# WIBL.net
KiCad netlist of a schematic drawn in EAGLE
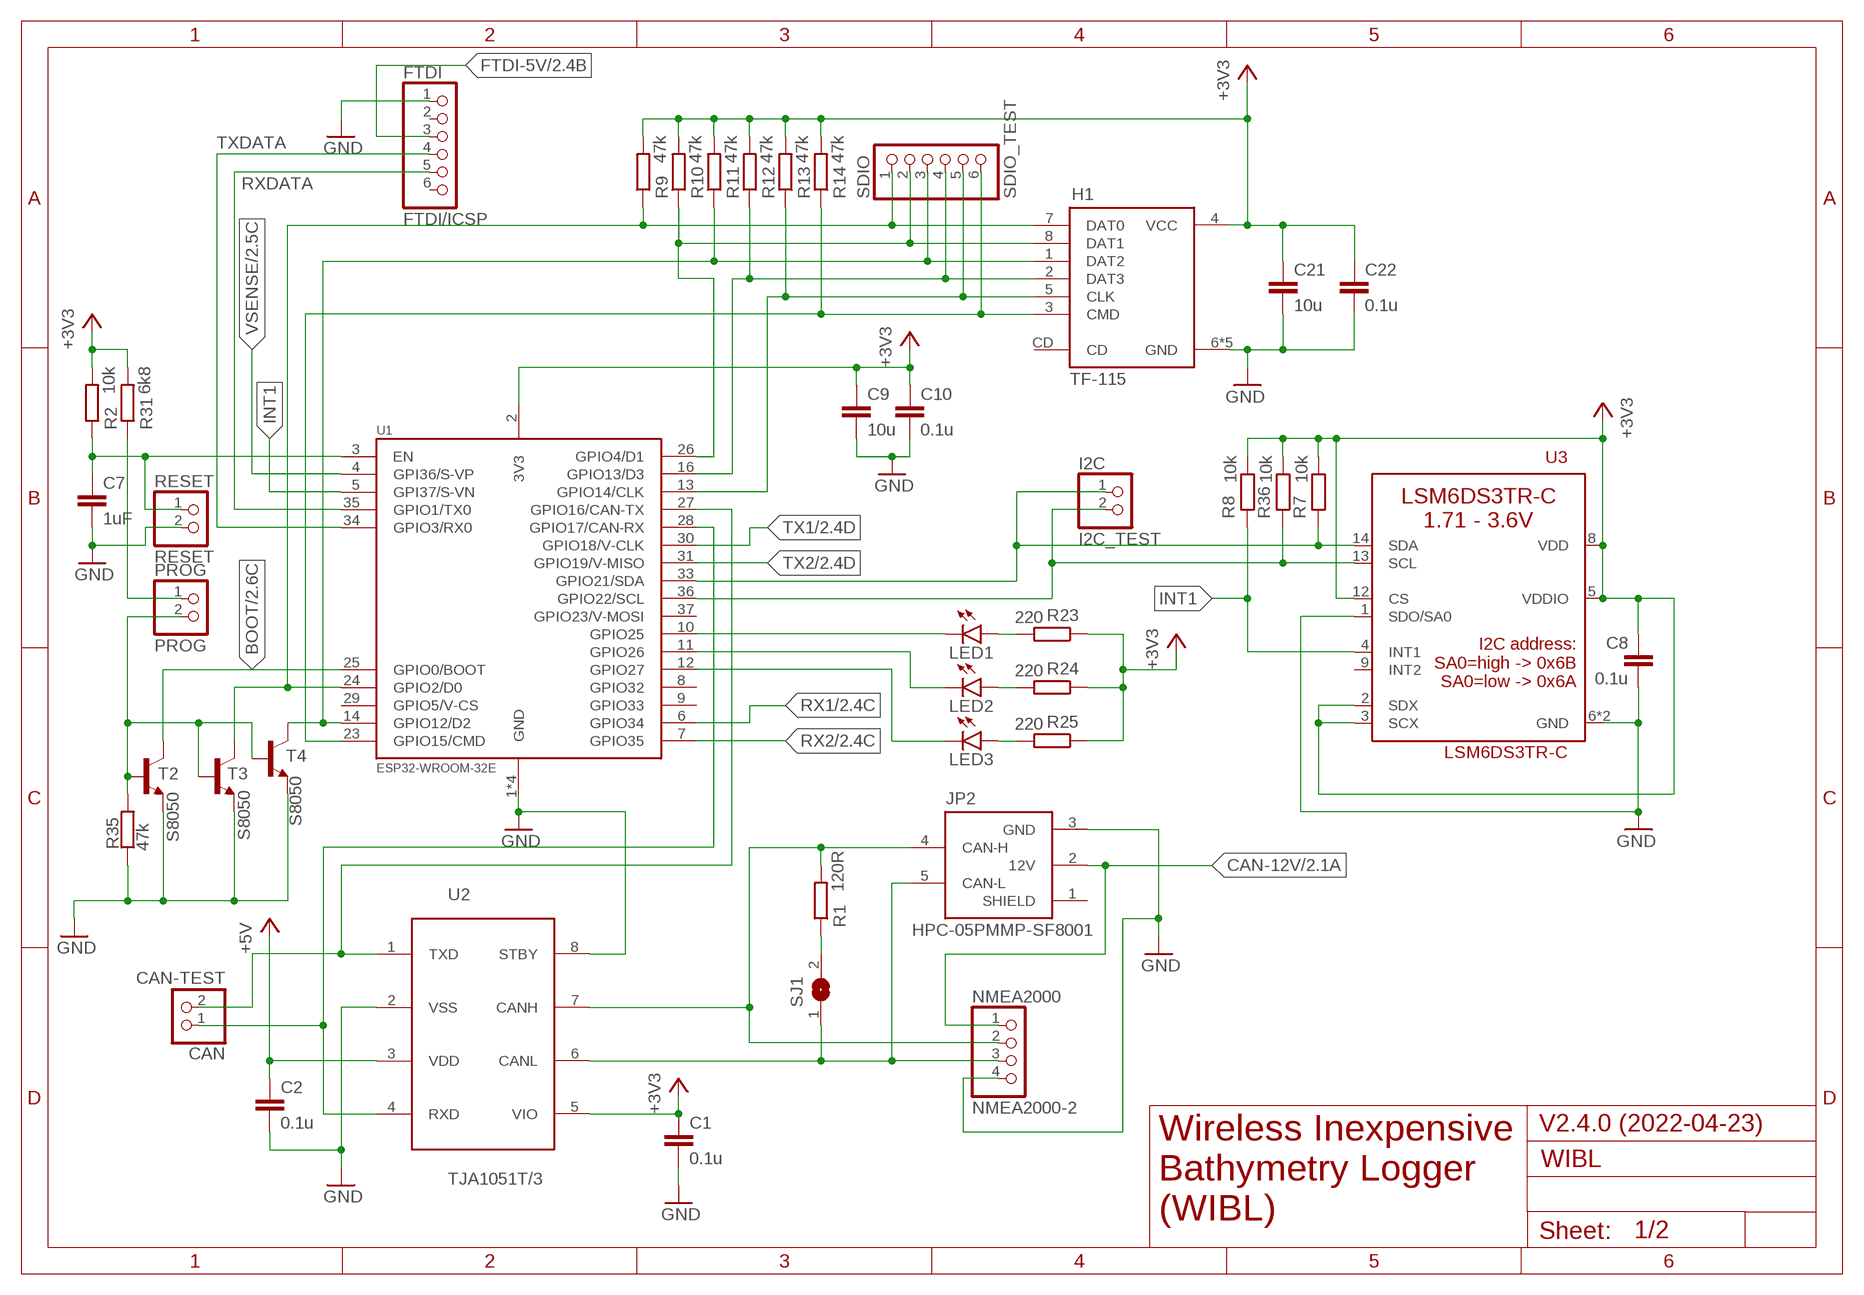
[diagram p0: schematic, sheet 1]
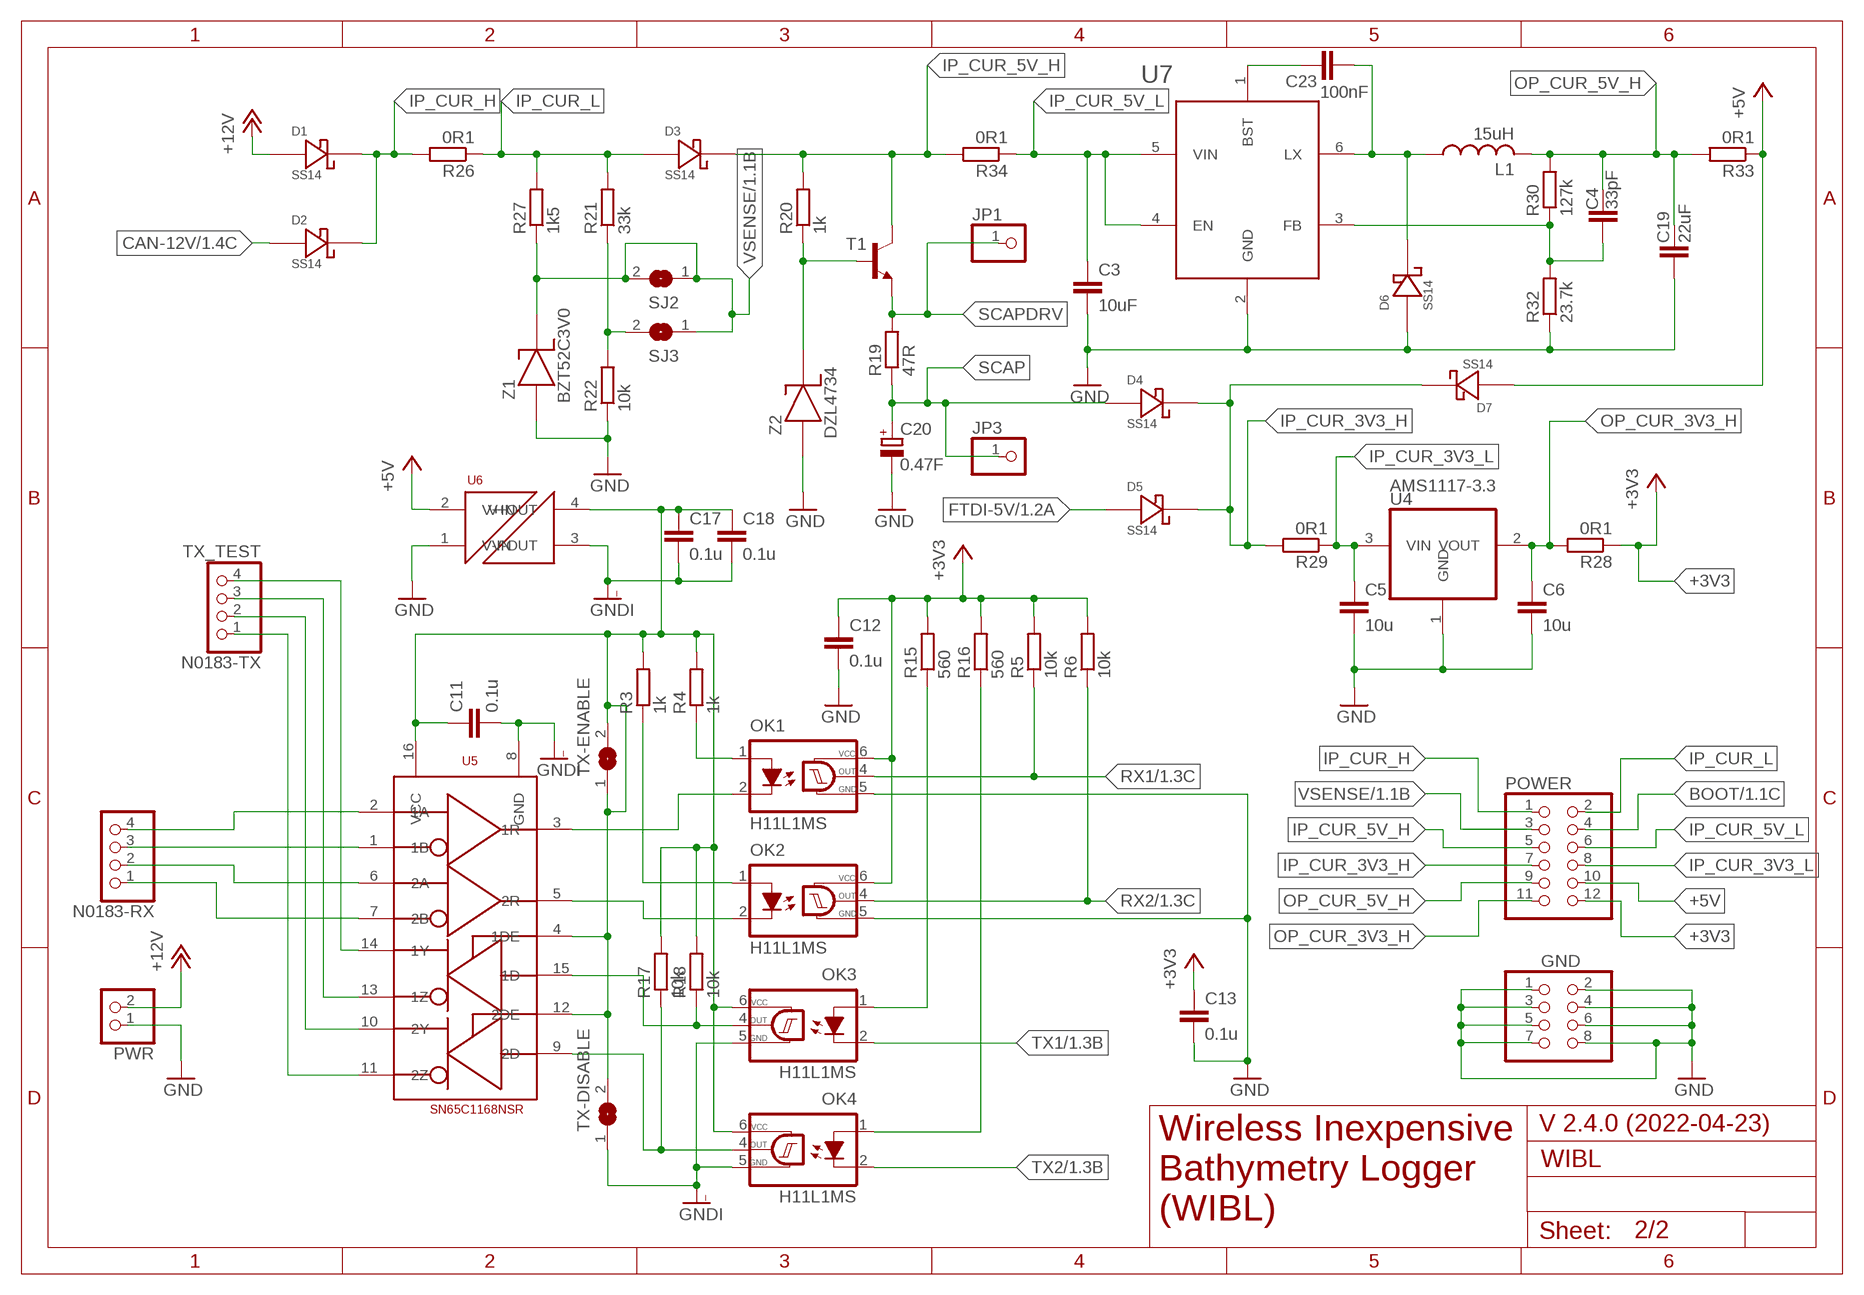
[diagram p1: schematic, sheet 2]

(export (version "E")
  (design (tool "Eeschema 10.0.6"))
  (components
    (comp (ref "C1")
      (value "0.1u")
      (footprint "eagle-import:C0805")
      (libsource (lib "eagle-import") (part "C-EUC0805"))
    )
    (comp (ref "C2")
      (value "0.1u")
      (footprint "eagle-import:C0805")
      (libsource (lib "eagle-import") (part "C-EUC0805"))
    )
    (comp (ref "C7")
      (value "1uF")
      (footprint "eagle-import:C0805")
      (libsource (lib "eagle-import") (part "C-EUC0805"))
    )
    (comp (ref "C8")
      (value "0.1u")
      (footprint "eagle-import:C0805")
      (libsource (lib "eagle-import") (part "C-EUC0805"))
    )
    (comp (ref "C9")
      (value "10u")
      (footprint "eagle-import:C0805")
      (libsource (lib "eagle-import") (part "C-EUC0805"))
    )
    (comp (ref "C10")
      (value "0.1u")
      (footprint "eagle-import:C0805")
      (libsource (lib "eagle-import") (part "C-EUC0805"))
    )
    (comp (ref "C21")
      (value "10u")
      (footprint "eagle-import:C0805")
      (libsource (lib "eagle-import") (part "C-EUC0805"))
    )
    (comp (ref "C22")
      (value "0.1u")
      (footprint "eagle-import:C0805")
      (libsource (lib "eagle-import") (part "C-EUC0805"))
    )
    (comp (ref "CAN")
      (value "CAN-TEST")
      (footprint "eagle-import:1X02")
      (libsource (lib "eagle-import") (part "PINHD-1X2"))
    )
    (comp (ref "FTDI")
      (value "FTDI/ICSP")
      (footprint "eagle-import:1X06")
      (libsource (lib "eagle-import") (part "PINHD-1X6"))
    )
    (comp (ref "H1")
      (value "TF-115")
      (footprint "eagle-import:XUNPU-MICROSD-SOCKET")
      (libsource (lib "eagle-import") (part "XUNPU-MICROSD-SOCKET"))
    )
    (comp (ref "I2C")
      (value "I2C_TEST")
      (footprint "eagle-import:1X02")
      (libsource (lib "eagle-import") (part "PINHD-1X2"))
    )
    (comp (ref "JP2")
      (value "HPC-05PMMP-SF8001")
      (footprint "eagle-import:NMEA2000")
      (libsource (lib "eagle-import") (part "NMEA2000"))
    )
    (comp (ref "LED1")
      (value "LEDCHIP-LED0603")
      (footprint "eagle-import:CHIP-LED0603")
      (libsource (lib "eagle-import") (part "LEDCHIP-LED0603"))
    )
    (comp (ref "LED2")
      (value "LEDCHIP-LED0603")
      (footprint "eagle-import:CHIP-LED0603")
      (libsource (lib "eagle-import") (part "LEDCHIP-LED0603"))
    )
    (comp (ref "LED3")
      (value "LEDCHIP-LED0603")
      (footprint "eagle-import:CHIP-LED0603")
      (libsource (lib "eagle-import") (part "LEDCHIP-LED0603"))
    )
    (comp (ref "NMEA2000")
      (value "NMEA2000-2")
      (footprint "eagle-import:1X04")
      (libsource (lib "eagle-import") (part "PINHD-1X4"))
    )
    (comp (ref "PROG")
      (value "PROG")
      (footprint "eagle-import:1X02")
      (libsource (lib "eagle-import") (part "PINHD-1X2"))
    )
    (comp (ref "R1")
      (value "120R")
      (footprint "eagle-import:R0805")
      (libsource (lib "eagle-import") (part "R-EU_R0805"))
    )
    (comp (ref "R2")
      (value "10k")
      (footprint "eagle-import:R0805")
      (libsource (lib "eagle-import") (part "R-EU_R0805"))
    )
    (comp (ref "R7")
      (value "10k")
      (footprint "eagle-import:R0805")
      (libsource (lib "eagle-import") (part "R-EU_R0805"))
    )
    (comp (ref "R8")
      (value "10k")
      (footprint "eagle-import:R0805")
      (libsource (lib "eagle-import") (part "R-EU_R0805"))
    )
    (comp (ref "R9")
      (value "47k")
      (footprint "eagle-import:R0805")
      (libsource (lib "eagle-import") (part "R-EU_R0805"))
    )
    (comp (ref "R10")
      (value "47k")
      (footprint "eagle-import:R0805")
      (libsource (lib "eagle-import") (part "R-EU_R0805"))
    )
    (comp (ref "R11")
      (value "47k")
      (footprint "eagle-import:R0805")
      (libsource (lib "eagle-import") (part "R-EU_R0805"))
    )
    (comp (ref "R12")
      (value "47k")
      (footprint "eagle-import:R0805")
      (libsource (lib "eagle-import") (part "R-EU_R0805"))
    )
    (comp (ref "R13")
      (value "47k")
      (footprint "eagle-import:R0805")
      (libsource (lib "eagle-import") (part "R-EU_R0805"))
    )
    (comp (ref "R14")
      (value "47k")
      (footprint "eagle-import:R0805")
      (libsource (lib "eagle-import") (part "R-EU_R0805"))
    )
    (comp (ref "R23")
      (value "220")
      (footprint "eagle-import:R0805")
      (libsource (lib "eagle-import") (part "R-EU_R0805"))
    )
    (comp (ref "R24")
      (value "220")
      (footprint "eagle-import:R0805")
      (libsource (lib "eagle-import") (part "R-EU_R0805"))
    )
    (comp (ref "R25")
      (value "220")
      (footprint "eagle-import:R0805")
      (libsource (lib "eagle-import") (part "R-EU_R0805"))
    )
    (comp (ref "R31")
      (value "6k8")
      (footprint "eagle-import:R0805")
      (libsource (lib "eagle-import") (part "R-EU_R0805"))
    )
    (comp (ref "R35")
      (value "47k")
      (footprint "eagle-import:R0805")
      (libsource (lib "eagle-import") (part "R-EU_R0805"))
    )
    (comp (ref "R36")
      (value "10k")
      (footprint "eagle-import:R0805")
      (libsource (lib "eagle-import") (part "R-EU_R0805"))
    )
    (comp (ref "RESET")
      (value "RESET")
      (footprint "eagle-import:1X02")
      (libsource (lib "eagle-import") (part "PINHD-1X2"))
    )
    (comp (ref "SDIO")
      (value "SDIO_TEST")
      (footprint "eagle-import:1X06")
      (libsource (lib "eagle-import") (part "PINHD-1X6"))
    )
    (comp (ref "SJ1") (value "SJ") (footprint "eagle-import:SJ") (libsource (lib "eagle-import") (part "SJ")))
    (comp (ref "T2")
      (value "S8050")
      (footprint "eagle-import:SOT23")
      (libsource (lib "eagle-import") (part "BC846"))
    )
    (comp (ref "T3")
      (value "S8050")
      (footprint "eagle-import:SOT23")
      (libsource (lib "eagle-import") (part "BC846"))
    )
    (comp (ref "T4")
      (value "S8050")
      (footprint "eagle-import:SOT23")
      (libsource (lib "eagle-import") (part "BC846"))
    )
    (comp (ref "U1")
      (value "ESP32-WROOM-32E")
      (footprint "eagle-import:ESPS32-WROOM-32E")
      (libsource (lib "eagle-import") (part "ESP32-WROOM-32E"))
    )
    (comp (ref "U2")
      (value "TJA1051T/3")
      (footprint "eagle-import:SOIC8")
      (libsource (lib "eagle-import") (part "MCP2562T-E/SN"))
    )
    (comp (ref "U3")
      (value "LSM6DS3TR-C")
      (footprint "eagle-import:LGA-14-2.5X3MM")
      (fields (field (name "MF") "STMicroelectronics"))
      (libsource (lib "eagle-import") (part "LSM6DS3TR-C"))
    )
    (comp (ref "C3")
      (value "10uF")
      (footprint "eagle-import:C1206")
      (libsource (lib "eagle-import") (part "C-EUC1206"))
    )
    (comp (ref "C4")
      (value "33pF")
      (footprint "eagle-import:C0603")
      (libsource (lib "eagle-import") (part "C-EUC0603"))
    )
    (comp (ref "C5")
      (value "10u")
      (footprint "eagle-import:C0805")
      (libsource (lib "eagle-import") (part "C-EUC0805"))
    )
    (comp (ref "C6")
      (value "10u")
      (footprint "eagle-import:C0805")
      (libsource (lib "eagle-import") (part "C-EUC0805"))
    )
    (comp (ref "C11")
      (value "0.1u")
      (footprint "eagle-import:C0805")
      (libsource (lib "eagle-import") (part "C-EUC0805"))
    )
    (comp (ref "C12")
      (value "0.1u")
      (footprint "eagle-import:C0805")
      (libsource (lib "eagle-import") (part "C-EUC0805"))
    )
    (comp (ref "C13")
      (value "0.1u")
      (footprint "eagle-import:C0805")
      (libsource (lib "eagle-import") (part "C-EUC0805"))
    )
    (comp (ref "C17")
      (value "0.1u")
      (footprint "eagle-import:C0805")
      (libsource (lib "eagle-import") (part "C-EUC0805"))
    )
    (comp (ref "C18")
      (value "0.1u")
      (footprint "eagle-import:C0805")
      (libsource (lib "eagle-import") (part "C-EUC0805"))
    )
    (comp (ref "C19")
      (value "22uF")
      (footprint "eagle-import:C0603")
      (libsource (lib "eagle-import") (part "C-EUC0603"))
    )
    (comp (ref "C20")
      (value "0.47F")
      (footprint "eagle-import:P128-50")
      (libsource (lib "eagle-import") (part "CPOL-EUP128-50"))
    )
    (comp (ref "C23")
      (value "100nF")
      (footprint "eagle-import:C0402")
      (libsource (lib "eagle-import") (part "C0402"))
    )
    (comp (ref "D1")
      (value "SS14")
      (footprint "eagle-import:DO-214AC")
      (libsource (lib "eagle-import") (part "SS14"))
    )
    (comp (ref "D2")
      (value "SS14")
      (footprint "eagle-import:DO-214AC")
      (libsource (lib "eagle-import") (part "SS14"))
    )
    (comp (ref "D3")
      (value "SS14")
      (footprint "eagle-import:DO-214AC")
      (libsource (lib "eagle-import") (part "SS14"))
    )
    (comp (ref "D4")
      (value "SS14")
      (footprint "eagle-import:DO-214AC")
      (libsource (lib "eagle-import") (part "SS14"))
    )
    (comp (ref "D5")
      (value "SS14")
      (footprint "eagle-import:DO-214AC")
      (libsource (lib "eagle-import") (part "SS14"))
    )
    (comp (ref "D6")
      (value "SS14")
      (footprint "eagle-import:DO-214AC")
      (libsource (lib "eagle-import") (part "SS14"))
    )
    (comp (ref "D7")
      (value "SS14")
      (footprint "eagle-import:DO-214AC")
      (libsource (lib "eagle-import") (part "SS14"))
    )
    (comp (ref "GND")
      (value "PINHD-2X4")
      (footprint "eagle-import:2X04")
      (libsource (lib "eagle-import") (part "PINHD-2X4"))
    )
    (comp (ref "JP1")
      (value "PINHD-1X1")
      (footprint "eagle-import:1X01")
      (libsource (lib "eagle-import") (part "PINHD-1X1"))
    )
    (comp (ref "JP3")
      (value "PINHD-1X1")
      (footprint "eagle-import:1X01")
      (libsource (lib "eagle-import") (part "PINHD-1X1"))
    )
    (comp (ref "L1")
      (value "15uH")
      (footprint "eagle-import:MWSA0603S")
      (libsource (lib "eagle-import") (part "MWSA0603S"))
    )
    (comp (ref "N0183-RX")
      (value "PINHD-1X4")
      (footprint "eagle-import:1X04")
      (libsource (lib "eagle-import") (part "PINHD-1X4"))
    )
    (comp (ref "N0183-TX")
      (value "TX_TEST")
      (footprint "eagle-import:1X04")
      (libsource (lib "eagle-import") (part "PINHD-1X4"))
    )
    (comp (ref "OK1")
      (value "H11L1MS")
      (footprint "eagle-import:DIL6-SMD")
      (libsource (lib "eagle-import") (part "H11LMS1"))
    )
    (comp (ref "OK2")
      (value "H11L1MS")
      (footprint "eagle-import:DIL6-SMD")
      (libsource (lib "eagle-import") (part "H11LMS1"))
    )
    (comp (ref "OK3")
      (value "H11L1MS")
      (footprint "eagle-import:DIL6-SMD")
      (libsource (lib "eagle-import") (part "H11LMS1"))
    )
    (comp (ref "OK4")
      (value "H11L1MS")
      (footprint "eagle-import:DIL6-SMD")
      (libsource (lib "eagle-import") (part "H11LMS1"))
    )
    (comp (ref "POWER")
      (value "PINHD-2X6")
      (footprint "eagle-import:2X06")
      (libsource (lib "eagle-import") (part "PINHD-2X6"))
    )
    (comp (ref "PWR")
      (value "PINHD-1X2")
      (footprint "eagle-import:1X02")
      (libsource (lib "eagle-import") (part "PINHD-1X2"))
    )
    (comp (ref "R3")
      (value "1k")
      (footprint "eagle-import:R0805")
      (libsource (lib "eagle-import") (part "R-EU_R0805"))
    )
    (comp (ref "R4")
      (value "1k")
      (footprint "eagle-import:R0805")
      (libsource (lib "eagle-import") (part "R-EU_R0805"))
    )
    (comp (ref "R5")
      (value "10k")
      (footprint "eagle-import:R0805")
      (libsource (lib "eagle-import") (part "R-EU_R0805"))
    )
    (comp (ref "R6")
      (value "10k")
      (footprint "eagle-import:R0805")
      (libsource (lib "eagle-import") (part "R-EU_R0805"))
    )
    (comp (ref "R15")
      (value "560")
      (footprint "eagle-import:R0805")
      (libsource (lib "eagle-import") (part "R-EU_R0805"))
    )
    (comp (ref "R16")
      (value "560")
      (footprint "eagle-import:R0805")
      (libsource (lib "eagle-import") (part "R-EU_R0805"))
    )
    (comp (ref "R17")
      (value "10k")
      (footprint "eagle-import:R0805")
      (libsource (lib "eagle-import") (part "R-EU_R0805"))
    )
    (comp (ref "R18")
      (value "10k")
      (footprint "eagle-import:R0805")
      (libsource (lib "eagle-import") (part "R-EU_R0805"))
    )
    (comp (ref "R19")
      (value "47R")
      (footprint "eagle-import:R0805")
      (libsource (lib "eagle-import") (part "R-EU_R0805"))
    )
    (comp (ref "R20")
      (value "1k")
      (footprint "eagle-import:R0805")
      (libsource (lib "eagle-import") (part "R-EU_R0805"))
    )
    (comp (ref "R21")
      (value "33k")
      (footprint "eagle-import:R0805")
      (libsource (lib "eagle-import") (part "R-EU_R0805"))
    )
    (comp (ref "R22")
      (value "10k")
      (footprint "eagle-import:R0805")
      (libsource (lib "eagle-import") (part "R-EU_R0805"))
    )
    (comp (ref "R26")
      (value "0R1")
      (footprint "eagle-import:R0603")
      (libsource (lib "eagle-import") (part "R-EU_R0603"))
    )
    (comp (ref "R27")
      (value "1k5")
      (footprint "eagle-import:R0805")
      (libsource (lib "eagle-import") (part "R-EU_R0805"))
    )
    (comp (ref "R28")
      (value "0R1")
      (footprint "eagle-import:R0603")
      (libsource (lib "eagle-import") (part "R-EU_R0603"))
    )
    (comp (ref "R29")
      (value "0R1")
      (footprint "eagle-import:R0603")
      (libsource (lib "eagle-import") (part "R-EU_R0603"))
    )
    (comp (ref "R30")
      (value "127k")
      (footprint "eagle-import:R0603")
      (libsource (lib "eagle-import") (part "R-EU_R0603"))
    )
    (comp (ref "R32")
      (value "23.7k")
      (footprint "eagle-import:R0603")
      (libsource (lib "eagle-import") (part "R-EU_R0603"))
    )
    (comp (ref "R33")
      (value "0R1")
      (footprint "eagle-import:R0603")
      (libsource (lib "eagle-import") (part "R-EU_R0603"))
    )
    (comp (ref "R34")
      (value "0R1")
      (footprint "eagle-import:R0603")
      (libsource (lib "eagle-import") (part "R-EU_R0603"))
    )
    (comp (ref "SJ2") (value "SJ") (footprint "eagle-import:SJ") (libsource (lib "eagle-import") (part "SJ")))
    (comp (ref "SJ3") (value "SJ") (footprint "eagle-import:SJ") (libsource (lib "eagle-import") (part "SJ")))
    (comp (ref "T1")
      (value "BC817-16-NPN-SOT23-BEC")
      (footprint "eagle-import:SOT23-BEC")
      (libsource (lib "eagle-import") (part "-NPN-SOT23-BECBC817-16"))
    )
    (comp (ref "TX-DISABLE")
      (value "SJ")
      (footprint "eagle-import:SJ")
      (libsource (lib "eagle-import") (part "SJ"))
    )
    (comp (ref "TX-ENABLE")
      (value "SJ")
      (footprint "eagle-import:SJ")
      (libsource (lib "eagle-import") (part "SJ"))
    )
    (comp (ref "U4")
      (value "AMS1117-3.3")
      (footprint "eagle-import:SOT223")
      (fields (field (name "MPN") "REG1117"))
      (libsource (lib "eagle-import") (part "REG1117"))
    )
    (comp (ref "U5")
      (value "SN65C1168NSR")
      (footprint "eagle-import:SOIC16")
      (libsource (lib "eagle-import") (part "SN65C1168-SOIC"))
    )
    (comp (ref "U6")
      (value "RFM-0505S")
      (footprint "eagle-import:RFM-0505S")
      (libsource (lib "eagle-import") (part "RFM-0505S"))
    )
    (comp (ref "U7")
      (value "BL9352A")
      (footprint "eagle-import:SOT-23-6L")
      (libsource (lib "eagle-import") (part "BL9352A"))
    )
    (comp (ref "Z1")
      (value "BZT52C3V0")
      (footprint "eagle-import:SOD123")
      (libsource (lib "eagle-import") (part "BZT52C3V0"))
    )
    (comp (ref "Z2")
      (value "DZL4734")
      (footprint "eagle-import:SOD-123FL")
      (libsource (lib "eagle-import") (part "DZL4734"))
    )
  )
  (nets
    (net (code "1") (name "+3V3") (class "Default")
      (node (ref "C1") (pin "1") (pinfunction "1_1") (pintype "passive"))
      (node (ref "C10") (pin "1") (pinfunction "1_1") (pintype "passive"))
      (node (ref "C12") (pin "1") (pinfunction "1_1") (pintype "passive"))
      (node (ref "C13") (pin "1") (pinfunction "1_1") (pintype "passive"))
      (node (ref "C21") (pin "1") (pinfunction "1_1") (pintype "passive"))
      (node (ref "C22") (pin "1") (pinfunction "1_1") (pintype "passive"))
      (node (ref "C8") (pin "1") (pinfunction "1_1") (pintype "passive"))
      (node (ref "C9") (pin "1") (pinfunction "1_1") (pintype "passive"))
      (node (ref "H1") (pin "4") (pinfunction "VCC_4") (pintype "bidirectional"))
      (node (ref "OK1") (pin "6") (pinfunction "VCC_6") (pintype "power_in"))
      (node (ref "OK2") (pin "6") (pinfunction "VCC_6") (pintype "power_in"))
      (node (ref "POWER") (pin "12") (pinfunction "12_12") (pintype "passive"))
      (node (ref "R10") (pin "2") (pinfunction "2_2") (pintype "passive"))
      (node (ref "R11") (pin "2") (pinfunction "2_2") (pintype "passive"))
      (node (ref "R12") (pin "2") (pinfunction "2_2") (pintype "passive"))
      (node (ref "R13") (pin "2") (pinfunction "2_2") (pintype "passive"))
      (node (ref "R14") (pin "2") (pinfunction "2_2") (pintype "passive"))
      (node (ref "R15") (pin "2") (pinfunction "2_2") (pintype "passive"))
      (node (ref "R16") (pin "2") (pinfunction "2_2") (pintype "passive"))
      (node (ref "R2") (pin "2") (pinfunction "2_2") (pintype "passive"))
      (node (ref "R23") (pin "1") (pinfunction "1_1") (pintype "passive"))
      (node (ref "R24") (pin "1") (pinfunction "1_1") (pintype "passive"))
      (node (ref "R25") (pin "1") (pinfunction "1_1") (pintype "passive"))
      (node (ref "R28") (pin "1") (pinfunction "1_1") (pintype "passive"))
      (node (ref "R31") (pin "2") (pinfunction "2_2") (pintype "passive"))
      (node (ref "R36") (pin "2") (pinfunction "2_2") (pintype "passive"))
      (node (ref "R5") (pin "2") (pinfunction "2_2") (pintype "passive"))
      (node (ref "R6") (pin "2") (pinfunction "2_2") (pintype "passive"))
      (node (ref "R7") (pin "2") (pinfunction "2_2") (pintype "passive"))
      (node (ref "R8") (pin "2") (pinfunction "2_2") (pintype "passive"))
      (node (ref "R9") (pin "2") (pinfunction "2_2") (pintype "passive"))
      (node (ref "U1") (pin "2") (pinfunction "3V3_2") (pintype "bidirectional"))
      (node (ref "U2") (pin "5") (pinfunction "VIO_5") (pintype "bidirectional"))
      (node (ref "U3") (pin "12") (pinfunction "CS_12") (pintype "bidirectional"))
      (node (ref "U3") (pin "2") (pinfunction "SDX_2") (pintype "bidirectional"))
      (node (ref "U3") (pin "3") (pinfunction "SCX_3") (pintype "bidirectional"))
      (node (ref "U3") (pin "5") (pinfunction "VDDIO_5") (pintype "bidirectional"))
      (node (ref "U3") (pin "8") (pinfunction "VDD_8") (pintype "bidirectional"))
    )
    (net (code "2") (name "+5V") (class "Default")
      (node (ref "C2") (pin "1") (pinfunction "1_1") (pintype "passive"))
      (node (ref "D7") (pin "A") (pinfunction "A_A") (pintype "bidirectional"))
      (node (ref "POWER") (pin "10") (pinfunction "10_10") (pintype "passive"))
      (node (ref "R33") (pin "1") (pinfunction "1_1") (pintype "passive"))
      (node (ref "U2") (pin "3") (pinfunction "VDD_3") (pintype "bidirectional"))
      (node (ref "U6") (pin "2") (pinfunction "V+IN_2") (pintype "bidirectional"))
    )
    (net (code "3") (name "+12V") (class "Default")
      (node (ref "D1") (pin "A") (pinfunction "A_A") (pintype "bidirectional"))
      (node (ref "PWR") (pin "2") (pinfunction "2_2") (pintype "passive"))
    )
    (net (code "4") (name "BOOT") (class "Default")
      (node (ref "POWER") (pin "4") (pinfunction "4_4") (pintype "passive"))
      (node (ref "T2") (pin "3") (pinfunction "C_3") (pintype "passive"))
      (node (ref "U1") (pin "25") (pinfunction "GPIO0/BOOT_25") (pintype "bidirectional"))
    )
    (net (code "5") (name "CAN-12V") (class "Default")
      (node (ref "D2") (pin "A") (pinfunction "A_A") (pintype "bidirectional"))
      (node (ref "JP2") (pin "2") (pinfunction "12V_2") (pintype "bidirectional"))
      (node (ref "NMEA2000") (pin "1") (pinfunction "1_1") (pintype "passive"))
    )
    (net (code "6") (name "FTDI-5V") (class "Default")
      (node (ref "D5") (pin "A") (pinfunction "A_A") (pintype "bidirectional"))
      (node (ref "FTDI") (pin "3") (pinfunction "3_3") (pintype "passive"))
    )
    (net (code "7") (name "GND") (class "Default")
      (node (ref "C1") (pin "2") (pinfunction "2_2") (pintype "passive"))
      (node (ref "C10") (pin "2") (pinfunction "2_2") (pintype "passive"))
      (node (ref "C12") (pin "2") (pinfunction "2_2") (pintype "passive"))
      (node (ref "C13") (pin "2") (pinfunction "2_2") (pintype "passive"))
      (node (ref "C19") (pin "1") (pinfunction "1_1") (pintype "passive"))
      (node (ref "C2") (pin "2") (pinfunction "2_2") (pintype "passive"))
      (node (ref "C20") (pin "-") (pinfunction "-_-") (pintype "passive"))
      (node (ref "C21") (pin "2") (pinfunction "2_2") (pintype "passive"))
      (node (ref "C22") (pin "2") (pinfunction "2_2") (pintype "passive"))
      (node (ref "C3") (pin "2") (pinfunction "2_2") (pintype "passive"))
      (node (ref "C5") (pin "2") (pinfunction "2_2") (pintype "passive"))
      (node (ref "C6") (pin "2") (pinfunction "2_2") (pintype "passive"))
      (node (ref "C7") (pin "2") (pinfunction "2_2") (pintype "passive"))
      (node (ref "C8") (pin "2") (pinfunction "2_2") (pintype "passive"))
      (node (ref "C9") (pin "2") (pinfunction "2_2") (pintype "passive"))
      (node (ref "D6") (pin "A") (pinfunction "A_A") (pintype "bidirectional"))
      (node (ref "FTDI") (pin "1") (pinfunction "1_1") (pintype "passive"))
      (node (ref "GND") (pin "1") (pinfunction "1_1") (pintype "passive"))
      (node (ref "GND") (pin "2") (pinfunction "2_2") (pintype "passive"))
      (node (ref "GND") (pin "3") (pinfunction "3_3") (pintype "passive"))
      (node (ref "GND") (pin "4") (pinfunction "4_4") (pintype "passive"))
      (node (ref "GND") (pin "5") (pinfunction "5_5") (pintype "passive"))
      (node (ref "GND") (pin "6") (pinfunction "6_6") (pintype "passive"))
      (node (ref "GND") (pin "7") (pinfunction "7_7") (pintype "passive"))
      (node (ref "GND") (pin "8") (pinfunction "8_8") (pintype "passive"))
      (node (ref "H1") (pin "6") (pinfunction "GND_6") (pintype "bidirectional"))
      (node (ref "H1") (pin "GND1") (pinfunction "GND_GND1") (pintype "bidirectional"))
      (node (ref "H1") (pin "GND2") (pinfunction "GND_GND2") (pintype "bidirectional"))
      (node (ref "H1") (pin "GND3") (pinfunction "GND_GND3") (pintype "bidirectional"))
      (node (ref "H1") (pin "GND4") (pinfunction "GND_GND4") (pintype "bidirectional"))
      (node (ref "JP2") (pin "3") (pinfunction "GND_3") (pintype "bidirectional"))
      (node (ref "NMEA2000") (pin "4") (pinfunction "4_4") (pintype "passive"))
      (node (ref "OK1") (pin "5") (pinfunction "GND_5") (pintype "power_in"))
      (node (ref "OK2") (pin "5") (pinfunction "GND_5") (pintype "power_in"))
      (node (ref "PWR") (pin "1") (pinfunction "1_1") (pintype "passive"))
      (node (ref "R22") (pin "1") (pinfunction "1_1") (pintype "passive"))
      (node (ref "R32") (pin "1") (pinfunction "1_1") (pintype "passive"))
      (node (ref "R35") (pin "1") (pinfunction "1_1") (pintype "passive"))
      (node (ref "RESET") (pin "2") (pinfunction "2_2") (pintype "passive"))
      (node (ref "T2") (pin "2") (pinfunction "E_2") (pintype "passive"))
      (node (ref "T3") (pin "2") (pinfunction "E_2") (pintype "passive"))
      (node (ref "T4") (pin "2") (pinfunction "E_2") (pintype "passive"))
      (node (ref "U1") (pin "1") (pinfunction "GND_1") (pintype "bidirectional"))
      (node (ref "U1") (pin "15") (pinfunction "GND_15") (pintype "bidirectional"))
      (node (ref "U1") (pin "38") (pinfunction "GND_38") (pintype "bidirectional"))
      (node (ref "U1") (pin "THERM") (pinfunction "GND_THERM") (pintype "bidirectional"))
      (node (ref "U2") (pin "2") (pinfunction "VSS_2") (pintype "bidirectional"))
      (node (ref "U2") (pin "8") (pinfunction "STBY_8") (pintype "bidirectional"))
      (node (ref "U3") (pin "1") (pinfunction "SDO/SA0_1") (pintype "bidirectional"))
      (node (ref "U3") (pin "6") (pinfunction "GND_6") (pintype "bidirectional"))
      (node (ref "U3") (pin "7") (pinfunction "GND_7") (pintype "bidirectional"))
      (node (ref "U4") (pin "1") (pinfunction "GND_1") (pintype "power_in"))
      (node (ref "U6") (pin "1") (pinfunction "V-IN_1") (pintype "bidirectional"))
      (node (ref "U7") (pin "2") (pinfunction "GND_2") (pintype "bidirectional"))
      (node (ref "Z1") (pin "1") (pinfunction "A_1") (pintype "bidirectional"))
      (node (ref "Z2") (pin "A") (pinfunction "A_A") (pintype "bidirectional"))
    )
    (net (code "8") (name "GNDI") (class "Default")
      (node (ref "C11") (pin "2") (pinfunction "2_2") (pintype "passive"))
      (node (ref "C17") (pin "2") (pinfunction "2_2") (pintype "passive"))
      (node (ref "C18") (pin "2") (pinfunction "2_2") (pintype "passive"))
      (node (ref "OK3") (pin "5") (pinfunction "GND_5") (pintype "power_in"))
      (node (ref "OK4") (pin "5") (pinfunction "GND_5") (pintype "power_in"))
      (node (ref "TX-DISABLE") (pin "1") (pinfunction "1_1") (pintype "passive"))
      (node (ref "U5") (pin "8") (pinfunction "GND_8") (pintype "bidirectional"))
      (node (ref "U6") (pin "3") (pinfunction "V-OUT_3") (pintype "bidirectional"))
    )
    (net (code "9") (name "INT1") (class "Default")
      (node (ref "R8") (pin "1") (pinfunction "1_1") (pintype "passive"))
      (node (ref "U1") (pin "5") (pinfunction "GPI37/S-VN_5") (pintype "bidirectional"))
      (node (ref "U3") (pin "4") (pinfunction "INT1_4") (pintype "bidirectional"))
    )
    (net (code "10") (name "IP_CUR_3V3_H") (class "Default")
      (node (ref "D4") (pin "K") (pinfunction "K_K") (pintype "bidirectional"))
      (node (ref "D5") (pin "K") (pinfunction "K_K") (pintype "bidirectional"))
      (node (ref "D7") (pin "K") (pinfunction "K_K") (pintype "bidirectional"))
      (node (ref "POWER") (pin "7") (pinfunction "7_7") (pintype "passive"))
      (node (ref "R29") (pin "2") (pinfunction "2_2") (pintype "passive"))
    )
    (net (code "11") (name "IP_CUR_3V3_L") (class "Default")
      (node (ref "C5") (pin "1") (pinfunction "1_1") (pintype "passive"))
      (node (ref "POWER") (pin "8") (pinfunction "8_8") (pintype "passive"))
      (node (ref "R29") (pin "1") (pinfunction "1_1") (pintype "passive"))
      (node (ref "U4") (pin "3") (pinfunction "VIN_3") (pintype "input"))
    )
    (net (code "12") (name "IP_CUR_5V_H") (class "Default")
      (node (ref "D3") (pin "K") (pinfunction "K_K") (pintype "bidirectional"))
      (node (ref "POWER") (pin "5") (pinfunction "5_5") (pintype "passive"))
      (node (ref "R20") (pin "2") (pinfunction "2_2") (pintype "passive"))
      (node (ref "R34") (pin "2") (pinfunction "2_2") (pintype "passive"))
      (node (ref "T1") (pin "C") (pinfunction "C_C") (pintype "passive"))
    )
    (net (code "13") (name "IP_CUR_5V_L") (class "Default")
      (node (ref "C3") (pin "1") (pinfunction "1_1") (pintype "passive"))
      (node (ref "POWER") (pin "6") (pinfunction "6_6") (pintype "passive"))
      (node (ref "R34") (pin "1") (pinfunction "1_1") (pintype "passive"))
      (node (ref "U7") (pin "4") (pinfunction "EN_4") (pintype "bidirectional"))
      (node (ref "U7") (pin "5") (pinfunction "VIN_5") (pintype "bidirectional"))
    )
    (net (code "14") (name "IP_CUR_H") (class "Default")
      (node (ref "D1") (pin "K") (pinfunction "K_K") (pintype "bidirectional"))
      (node (ref "D2") (pin "K") (pinfunction "K_K") (pintype "bidirectional"))
      (node (ref "POWER") (pin "1") (pinfunction "1_1") (pintype "passive"))
      (node (ref "R26") (pin "2") (pinfunction "2_2") (pintype "passive"))
    )
    (net (code "15") (name "IP_CUR_L") (class "Default")
      (node (ref "D3") (pin "A") (pinfunction "A_A") (pintype "bidirectional"))
      (node (ref "POWER") (pin "2") (pinfunction "2_2") (pintype "passive"))
      (node (ref "R21") (pin "2") (pinfunction "2_2") (pintype "passive"))
      (node (ref "R26") (pin "1") (pinfunction "1_1") (pintype "passive"))
      (node (ref "R27") (pin "2") (pinfunction "2_2") (pintype "passive"))
    )
    (net (code "16") (name "Net-(C23-1)") (class "Default")
      (node (ref "C23") (pin "P$1") (pinfunction "1_P$1") (pintype "passive"))
      (node (ref "U7") (pin "1") (pinfunction "BST_1") (pintype "bidirectional"))
    )
    (net (code "17") (name "Net-(C23-2)") (class "Default")
      (node (ref "C23") (pin "P$2") (pinfunction "2_P$2") (pintype "passive"))
      (node (ref "D6") (pin "K") (pinfunction "K_K") (pintype "bidirectional"))
      (node (ref "L1") (pin "P$1") (pinfunction "1_P$1") (pintype "passive"))
      (node (ref "U7") (pin "6") (pinfunction "LX_6") (pintype "bidirectional"))
    )
    (net (code "18") (name "Net-(H1-CLK)") (class "Default")
      (node (ref "H1") (pin "5") (pinfunction "CLK_5") (pintype "bidirectional"))
      (node (ref "R13") (pin "1") (pinfunction "1_1") (pintype "passive"))
      (node (ref "SDIO") (pin "5") (pinfunction "5_5") (pintype "passive"))
      (node (ref "U1") (pin "13") (pinfunction "GPIO14/CLK_13") (pintype "bidirectional"))
    )
    (net (code "19") (name "Net-(H1-CMD)") (class "Default")
      (node (ref "H1") (pin "3") (pinfunction "CMD_3") (pintype "bidirectional"))
      (node (ref "R14") (pin "1") (pinfunction "1_1") (pintype "passive"))
      (node (ref "SDIO") (pin "6") (pinfunction "6_6") (pintype "passive"))
      (node (ref "U1") (pin "23") (pinfunction "GPIO15/CMD_23") (pintype "bidirectional"))
    )
    (net (code "20") (name "Net-(H1-DAT0)") (class "Default")
      (node (ref "H1") (pin "7") (pinfunction "DAT0_7") (pintype "bidirectional"))
      (node (ref "R9") (pin "1") (pinfunction "1_1") (pintype "passive"))
      (node (ref "SDIO") (pin "1") (pinfunction "1_1") (pintype "passive"))
      (node (ref "T3") (pin "3") (pinfunction "C_3") (pintype "passive"))
      (node (ref "U1") (pin "24") (pinfunction "GPIO2/D0_24") (pintype "bidirectional"))
    )
    (net (code "21") (name "Net-(H1-DAT1)") (class "Default")
      (node (ref "H1") (pin "8") (pinfunction "DAT1_8") (pintype "bidirectional"))
      (node (ref "R10") (pin "1") (pinfunction "1_1") (pintype "passive"))
      (node (ref "SDIO") (pin "2") (pinfunction "2_2") (pintype "passive"))
      (node (ref "U1") (pin "26") (pinfunction "GPIO4/D1_26") (pintype "bidirectional"))
    )
    (net (code "22") (name "Net-(H1-DAT2)") (class "Default")
      (node (ref "H1") (pin "1") (pinfunction "DAT2_1") (pintype "bidirectional"))
      (node (ref "R11") (pin "1") (pinfunction "1_1") (pintype "passive"))
      (node (ref "SDIO") (pin "3") (pinfunction "3_3") (pintype "passive"))
      (node (ref "T4") (pin "3") (pinfunction "C_3") (pintype "passive"))
      (node (ref "U1") (pin "14") (pinfunction "GPIO12/D2_14") (pintype "bidirectional"))
    )
    (net (code "23") (name "Net-(H1-DAT3)") (class "Default")
      (node (ref "H1") (pin "2") (pinfunction "DAT3_2") (pintype "bidirectional"))
      (node (ref "R12") (pin "1") (pinfunction "1_1") (pintype "passive"))
      (node (ref "SDIO") (pin "4") (pinfunction "4_4") (pintype "passive"))
      (node (ref "U1") (pin "16") (pinfunction "GPIO13/D3_16") (pintype "bidirectional"))
    )
    (net (code "24") (name "Net-(JP2-CAN-H)") (class "Default")
      (node (ref "JP2") (pin "4") (pinfunction "CAN-H_4") (pintype "bidirectional"))
      (node (ref "NMEA2000") (pin "2") (pinfunction "2_2") (pintype "passive"))
      (node (ref "R1") (pin "2") (pinfunction "2_2") (pintype "passive"))
      (node (ref "U2") (pin "7") (pinfunction "CANH_7") (pintype "bidirectional"))
    )
    (net (code "25") (name "Net-(JP2-CAN-L)") (class "Default")
      (node (ref "JP2") (pin "5") (pinfunction "CAN-L_5") (pintype "bidirectional"))
      (node (ref "NMEA2000") (pin "3") (pinfunction "3_3") (pintype "passive"))
      (node (ref "SJ1") (pin "1") (pinfunction "1_1") (pintype "passive"))
      (node (ref "U2") (pin "6") (pinfunction "CANL_6") (pintype "bidirectional"))
    )
    (net (code "26") (name "Net-(LED1-PadA)") (class "Default")
      (node (ref "LED1") (pin "A") (pinfunction "A_A") (pintype "passive"))
      (node (ref "R23") (pin "2") (pinfunction "2_2") (pintype "passive"))
    )
    (net (code "27") (name "Net-(LED2-PadA)") (class "Default")
      (node (ref "LED2") (pin "A") (pinfunction "A_A") (pintype "passive"))
      (node (ref "R24") (pin "2") (pinfunction "2_2") (pintype "passive"))
    )
    (net (code "28") (name "Net-(LED3-PadA)") (class "Default")
      (node (ref "LED3") (pin "A") (pinfunction "A_A") (pintype "passive"))
      (node (ref "R25") (pin "2") (pinfunction "2_2") (pintype "passive"))
    )
    (net (code "29") (name "Net-(OK1-A)") (class "Default")
      (node (ref "OK1") (pin "1") (pinfunction "A_1") (pintype "passive"))
      (node (ref "R4") (pin "1") (pinfunction "1_1") (pintype "passive"))
    )
    (net (code "30") (name "Net-(OK1-C)") (class "Default")
      (node (ref "OK1") (pin "2") (pinfunction "C_2") (pintype "passive"))
      (node (ref "U5") (pin "3") (pinfunction "1R_3") (pintype "bidirectional"))
    )
    (net (code "31") (name "Net-(OK2-A)") (class "Default")
      (node (ref "OK2") (pin "1") (pinfunction "A_1") (pintype "passive"))
      (node (ref "R3") (pin "1") (pinfunction "1_1") (pintype "passive"))
    )
    (net (code "32") (name "Net-(OK2-C)") (class "Default")
      (node (ref "OK2") (pin "2") (pinfunction "C_2") (pintype "passive"))
      (node (ref "U5") (pin "5") (pinfunction "2R_5") (pintype "bidirectional"))
    )
    (net (code "33") (name "Net-(OK3-A)") (class "Default")
      (node (ref "OK3") (pin "1") (pinfunction "A_1") (pintype "passive"))
      (node (ref "R15") (pin "1") (pinfunction "1_1") (pintype "passive"))
    )
    (net (code "34") (name "Net-(OK3-OUT)") (class "Default")
      (node (ref "OK3") (pin "4") (pinfunction "OUT_4") (pintype "output"))
      (node (ref "R18") (pin "1") (pinfunction "1_1") (pintype "passive"))
      (node (ref "U5") (pin "15") (pinfunction "1D_15") (pintype "bidirectional"))
    )
    (net (code "35") (name "Net-(OK3-VCC)") (class "Default")
      (node (ref "C11") (pin "1") (pinfunction "1_1") (pintype "passive"))
      (node (ref "C17") (pin "1") (pinfunction "1_1") (pintype "passive"))
      (node (ref "C18") (pin "1") (pinfunction "1_1") (pintype "passive"))
      (node (ref "OK3") (pin "6") (pinfunction "VCC_6") (pintype "power_in"))
      (node (ref "OK4") (pin "6") (pinfunction "VCC_6") (pintype "power_in"))
      (node (ref "R17") (pin "2") (pinfunction "2_2") (pintype "passive"))
      (node (ref "R18") (pin "2") (pinfunction "2_2") (pintype "passive"))
      (node (ref "R3") (pin "2") (pinfunction "2_2") (pintype "passive"))
      (node (ref "R4") (pin "2") (pinfunction "2_2") (pintype "passive"))
      (node (ref "TX-DISABLE") (pin "2") (pinfunction "2_2") (pintype "passive"))
      (node (ref "TX-ENABLE") (pin "1") (pinfunction "1_1") (pintype "passive"))
      (node (ref "TX-ENABLE") (pin "2") (pinfunction "2_2") (pintype "passive"))
      (node (ref "U5") (pin "12") (pinfunction "2DE_12") (pintype "bidirectional"))
      (node (ref "U5") (pin "16") (pinfunction "VCC_16") (pintype "bidirectional"))
      (node (ref "U5") (pin "4") (pinfunction "1DE_4") (pintype "bidirectional"))
      (node (ref "U6") (pin "4") (pinfunction "V+OUT_4") (pintype "bidirectional"))
    )
    (net (code "36") (name "Net-(OK4-A)") (class "Default")
      (node (ref "OK4") (pin "1") (pinfunction "A_1") (pintype "passive"))
      (node (ref "R16") (pin "1") (pinfunction "1_1") (pintype "passive"))
    )
    (net (code "37") (name "Net-(OK4-OUT)") (class "Default")
      (node (ref "OK4") (pin "4") (pinfunction "OUT_4") (pintype "output"))
      (node (ref "R17") (pin "1") (pinfunction "1_1") (pintype "passive"))
      (node (ref "U5") (pin "9") (pinfunction "2D_9") (pintype "bidirectional"))
    )
    (net (code "38") (name "Net-(PROG-Pad1)") (class "Default")
      (node (ref "PROG") (pin "1") (pinfunction "1_1") (pintype "passive"))
      (node (ref "R31") (pin "1") (pinfunction "1_1") (pintype "passive"))
    )
    (net (code "39") (name "Net-(R1-Pad1)") (class "Default")
      (node (ref "R1") (pin "1") (pinfunction "1_1") (pintype "passive"))
      (node (ref "SJ1") (pin "2") (pinfunction "2_2") (pintype "passive"))
    )
    (net (code "40") (name "Net-(R20-Pad1)") (class "Default")
      (node (ref "R20") (pin "1") (pinfunction "1_1") (pintype "passive"))
      (node (ref "T1") (pin "B") (pinfunction "B_B") (pintype "passive"))
      (node (ref "Z2") (pin "K") (pinfunction "K_K") (pintype "bidirectional"))
    )
    (net (code "41") (name "Net-(R21-Pad1)") (class "Default")
      (node (ref "R21") (pin "1") (pinfunction "1_1") (pintype "passive"))
      (node (ref "R22") (pin "2") (pinfunction "2_2") (pintype "passive"))
      (node (ref "SJ3") (pin "2") (pinfunction "2_2") (pintype "passive"))
    )
    (net (code "42") (name "Net-(T2-B)") (class "Default")
      (node (ref "PROG") (pin "2") (pinfunction "2_2") (pintype "passive"))
      (node (ref "R35") (pin "2") (pinfunction "2_2") (pintype "passive"))
      (node (ref "T2") (pin "1") (pinfunction "B_1") (pintype "passive"))
      (node (ref "T3") (pin "1") (pinfunction "B_1") (pintype "passive"))
      (node (ref "T4") (pin "1") (pinfunction "B_1") (pintype "passive"))
    )
    (net (code "43") (name "Net-(U1-EN)") (class "Default")
      (node (ref "C7") (pin "1") (pinfunction "1_1") (pintype "passive"))
      (node (ref "R2") (pin "1") (pinfunction "1_1") (pintype "passive"))
      (node (ref "RESET") (pin "1") (pinfunction "1_1") (pintype "passive"))
      (node (ref "U1") (pin "3") (pinfunction "EN_3") (pintype "bidirectional"))
    )
    (net (code "44") (name "Net-(U1-GPIO16{slash}CAN-TX)") (class "Default")
      (node (ref "CAN") (pin "2") (pinfunction "2_2") (pintype "passive"))
      (node (ref "U1") (pin "27") (pinfunction "GPIO16/CAN-TX_27") (pintype "bidirectional"))
      (node (ref "U2") (pin "1") (pinfunction "TXD_1") (pintype "bidirectional"))
    )
    (net (code "45") (name "Net-(U1-GPIO17{slash}CAN-RX)") (class "Default")
      (node (ref "CAN") (pin "1") (pinfunction "1_1") (pintype "passive"))
      (node (ref "U1") (pin "28") (pinfunction "GPIO17/CAN-RX_28") (pintype "bidirectional"))
      (node (ref "U2") (pin "4") (pinfunction "RXD_4") (pintype "bidirectional"))
    )
    (net (code "46") (name "Net-(U1-GPIO21{slash}SDA)") (class "Default")
      (node (ref "I2C") (pin "1") (pinfunction "1_1") (pintype "passive"))
      (node (ref "R7") (pin "1") (pinfunction "1_1") (pintype "passive"))
      (node (ref "U1") (pin "33") (pinfunction "GPIO21/SDA_33") (pintype "bidirectional"))
      (node (ref "U3") (pin "14") (pinfunction "SDA_14") (pintype "bidirectional"))
    )
    (net (code "47") (name "Net-(U1-GPIO22{slash}SCL)") (class "Default")
      (node (ref "I2C") (pin "2") (pinfunction "2_2") (pintype "passive"))
      (node (ref "R36") (pin "1") (pinfunction "1_1") (pintype "passive"))
      (node (ref "U1") (pin "36") (pinfunction "GPIO22/SCL_36") (pintype "bidirectional"))
      (node (ref "U3") (pin "13") (pinfunction "SCL_13") (pintype "bidirectional"))
    )
    (net (code "48") (name "Net-(U1-GPIO25)") (class "Default")
      (node (ref "LED1") (pin "C") (pinfunction "C_C") (pintype "passive"))
      (node (ref "U1") (pin "10") (pinfunction "GPIO25_10") (pintype "bidirectional"))
    )
    (net (code "49") (name "Net-(U1-GPIO26)") (class "Default")
      (node (ref "LED2") (pin "C") (pinfunction "C_C") (pintype "passive"))
      (node (ref "U1") (pin "11") (pinfunction "GPIO26_11") (pintype "bidirectional"))
    )
    (net (code "50") (name "Net-(U1-GPIO27)") (class "Default")
      (node (ref "LED3") (pin "C") (pinfunction "C_C") (pintype "passive"))
      (node (ref "U1") (pin "12") (pinfunction "GPIO27_12") (pintype "bidirectional"))
    )
    (net (code "51") (name "Net-(U5-1A)") (class "Default")
      (node (ref "N0183-RX") (pin "4") (pinfunction "4_4") (pintype "passive"))
      (node (ref "U5") (pin "2") (pinfunction "1A_2") (pintype "bidirectional"))
    )
    (net (code "52") (name "Net-(U5-1B)") (class "Default")
      (node (ref "N0183-RX") (pin "3") (pinfunction "3_3") (pintype "passive"))
      (node (ref "U5") (pin "1") (pinfunction "1B_1") (pintype "bidirectional"))
    )
    (net (code "53") (name "Net-(U5-1Y)") (class "Default")
      (node (ref "N0183-TX") (pin "4") (pinfunction "4_4") (pintype "passive"))
      (node (ref "U5") (pin "14") (pinfunction "1Y_14") (pintype "bidirectional"))
    )
    (net (code "54") (name "Net-(U5-1Z)") (class "Default")
      (node (ref "N0183-TX") (pin "3") (pinfunction "3_3") (pintype "passive"))
      (node (ref "U5") (pin "13") (pinfunction "1Z_13") (pintype "bidirectional"))
    )
    (net (code "55") (name "Net-(U5-2A)") (class "Default")
      (node (ref "N0183-RX") (pin "2") (pinfunction "2_2") (pintype "passive"))
      (node (ref "U5") (pin "6") (pinfunction "2A_6") (pintype "bidirectional"))
    )
    (net (code "56") (name "Net-(U5-2B)") (class "Default")
      (node (ref "N0183-RX") (pin "1") (pinfunction "1_1") (pintype "passive"))
      (node (ref "U5") (pin "7") (pinfunction "2B_7") (pintype "bidirectional"))
    )
    (net (code "57") (name "Net-(U5-2Y)") (class "Default")
      (node (ref "N0183-TX") (pin "2") (pinfunction "2_2") (pintype "passive"))
      (node (ref "U5") (pin "10") (pinfunction "2Y_10") (pintype "bidirectional"))
    )
    (net (code "58") (name "Net-(U5-2Z)") (class "Default")
      (node (ref "N0183-TX") (pin "1") (pinfunction "1_1") (pintype "passive"))
      (node (ref "U5") (pin "11") (pinfunction "2Z_11") (pintype "bidirectional"))
    )
    (net (code "59") (name "Net-(U7-FB)") (class "Default")
      (node (ref "C4") (pin "1") (pinfunction "1_1") (pintype "passive"))
      (node (ref "R30") (pin "1") (pinfunction "1_1") (pintype "passive"))
      (node (ref "R32") (pin "2") (pinfunction "2_2") (pintype "passive"))
      (node (ref "U7") (pin "3") (pinfunction "FB_3") (pintype "bidirectional"))
    )
    (net (code "60") (name "OP_CUR_3V3_H") (class "Default")
      (node (ref "C6") (pin "1") (pinfunction "1_1") (pintype "passive"))
      (node (ref "POWER") (pin "11") (pinfunction "11_11") (pintype "passive"))
      (node (ref "R28") (pin "2") (pinfunction "2_2") (pintype "passive"))
      (node (ref "U4") (pin "2") (pinfunction "VOUT_2") (pintype "output"))
    )
    (net (code "61") (name "OP_CUR_5V_H") (class "Default")
      (node (ref "C19") (pin "2") (pinfunction "2_2") (pintype "passive"))
      (node (ref "C4") (pin "2") (pinfunction "2_2") (pintype "passive"))
      (node (ref "L1") (pin "P$2") (pinfunction "2_P$2") (pintype "passive"))
      (node (ref "POWER") (pin "9") (pinfunction "9_9") (pintype "passive"))
      (node (ref "R30") (pin "2") (pinfunction "2_2") (pintype "passive"))
      (node (ref "R33") (pin "2") (pinfunction "2_2") (pintype "passive"))
    )
    (net (code "62") (name "RX1") (class "Default")
      (node (ref "OK1") (pin "4") (pinfunction "OUT_4") (pintype "output"))
      (node (ref "R5") (pin "1") (pinfunction "1_1") (pintype "passive"))
      (node (ref "U1") (pin "6") (pinfunction "GPIO34_6") (pintype "bidirectional"))
    )
    (net (code "63") (name "RX2") (class "Default")
      (node (ref "OK2") (pin "4") (pinfunction "OUT_4") (pintype "output"))
      (node (ref "R6") (pin "1") (pinfunction "1_1") (pintype "passive"))
      (node (ref "U1") (pin "7") (pinfunction "GPIO35_7") (pintype "bidirectional"))
    )
    (net (code "64") (name "RXDATA") (class "Default")
      (node (ref "FTDI") (pin "5") (pinfunction "5_5") (pintype "passive"))
      (node (ref "U1") (pin "35") (pinfunction "GPIO1/TX0_35") (pintype "bidirectional"))
    )
    (net (code "65") (name "SCAP") (class "Default")
      (node (ref "C20") (pin "+") (pinfunction "+_+") (pintype "passive"))
      (node (ref "D4") (pin "A") (pinfunction "A_A") (pintype "bidirectional"))
      (node (ref "JP3") (pin "1") (pinfunction "1_1") (pintype "passive"))
      (node (ref "R19") (pin "1") (pinfunction "1_1") (pintype "passive"))
    )
    (net (code "66") (name "SCAPDRV") (class "Default")
      (node (ref "JP1") (pin "1") (pinfunction "1_1") (pintype "passive"))
      (node (ref "R19") (pin "2") (pinfunction "2_2") (pintype "passive"))
      (node (ref "T1") (pin "E") (pinfunction "E_E") (pintype "passive"))
    )
    (net (code "67") (name "TX1") (class "Default")
      (node (ref "OK3") (pin "2") (pinfunction "C_2") (pintype "passive"))
      (node (ref "U1") (pin "30") (pinfunction "GPIO18/V-CLK_30") (pintype "bidirectional"))
    )
    (net (code "68") (name "TX2") (class "Default")
      (node (ref "OK4") (pin "2") (pinfunction "C_2") (pintype "passive"))
      (node (ref "U1") (pin "31") (pinfunction "GPIO19/V-MISO_31") (pintype "bidirectional"))
    )
    (net (code "69") (name "TXDATA") (class "Default")
      (node (ref "FTDI") (pin "4") (pinfunction "4_4") (pintype "passive"))
      (node (ref "U1") (pin "34") (pinfunction "GPIO3/RX0_34") (pintype "bidirectional"))
    )
    (net (code "70") (name "VSENSE") (class "Default")
      (node (ref "POWER") (pin "3") (pinfunction "3_3") (pintype "passive"))
      (node (ref "R27") (pin "1") (pinfunction "1_1") (pintype "passive"))
      (node (ref "SJ2") (pin "1") (pinfunction "1_1") (pintype "passive"))
      (node (ref "SJ2") (pin "2") (pinfunction "2_2") (pintype "passive"))
      (node (ref "SJ3") (pin "1") (pinfunction "1_1") (pintype "passive"))
      (node (ref "U1") (pin "4") (pinfunction "GPI36/S-VP_4") (pintype "bidirectional"))
      (node (ref "Z1") (pin "2") (pinfunction "K_2") (pintype "bidirectional"))
    )
    (net (code "71") (name "unconnected-(FTDI-Pad2)") (class "Default")
      (node (ref "FTDI") (pin "2") (pinfunction "2_2") (pintype "passive"))
    )
    (net (code "72") (name "unconnected-(FTDI-Pad6)") (class "Default")
      (node (ref "FTDI") (pin "6") (pinfunction "6_6") (pintype "passive"))
    )
    (net (code "73") (name "unconnected-(H1-PadCD)") (class "Default")
      (node (ref "H1") (pin "CD") (pinfunction "CD_CD") (pintype "bidirectional"))
    )
    (net (code "74") (name "unconnected-(JP2-SHIELD-Pad1)") (class "Default")
      (node (ref "JP2") (pin "1") (pinfunction "SHIELD_1") (pintype "bidirectional"))
    )
    (net (code "75") (name "unconnected-(U1-GPIO5{slash}V-CS-Pad29)") (class "Default")
      (node (ref "U1") (pin "29") (pinfunction "GPIO5/V-CS_29") (pintype "bidirectional"))
    )
    (net (code "76") (name "unconnected-(U1-GPIO23{slash}V-MOSI-Pad37)") (class "Default")
      (node (ref "U1") (pin "37") (pinfunction "GPIO23/V-MOSI_37") (pintype "bidirectional"))
    )
    (net (code "77") (name "unconnected-(U1-GPIO32-Pad8)") (class "Default")
      (node (ref "U1") (pin "8") (pinfunction "GPIO32_8") (pintype "bidirectional"))
    )
    (net (code "78") (name "unconnected-(U1-GPIO33-Pad9)") (class "Default")
      (node (ref "U1") (pin "9") (pinfunction "GPIO33_9") (pintype "bidirectional"))
    )
    (net (code "79") (name "unconnected-(U3-INT2-Pad9)") (class "Default")
      (node (ref "U3") (pin "9") (pinfunction "INT2_9") (pintype "bidirectional"))
    )
  )
)
